# arwe.net
KiCad netlist of a schematic drawn in EAGLE
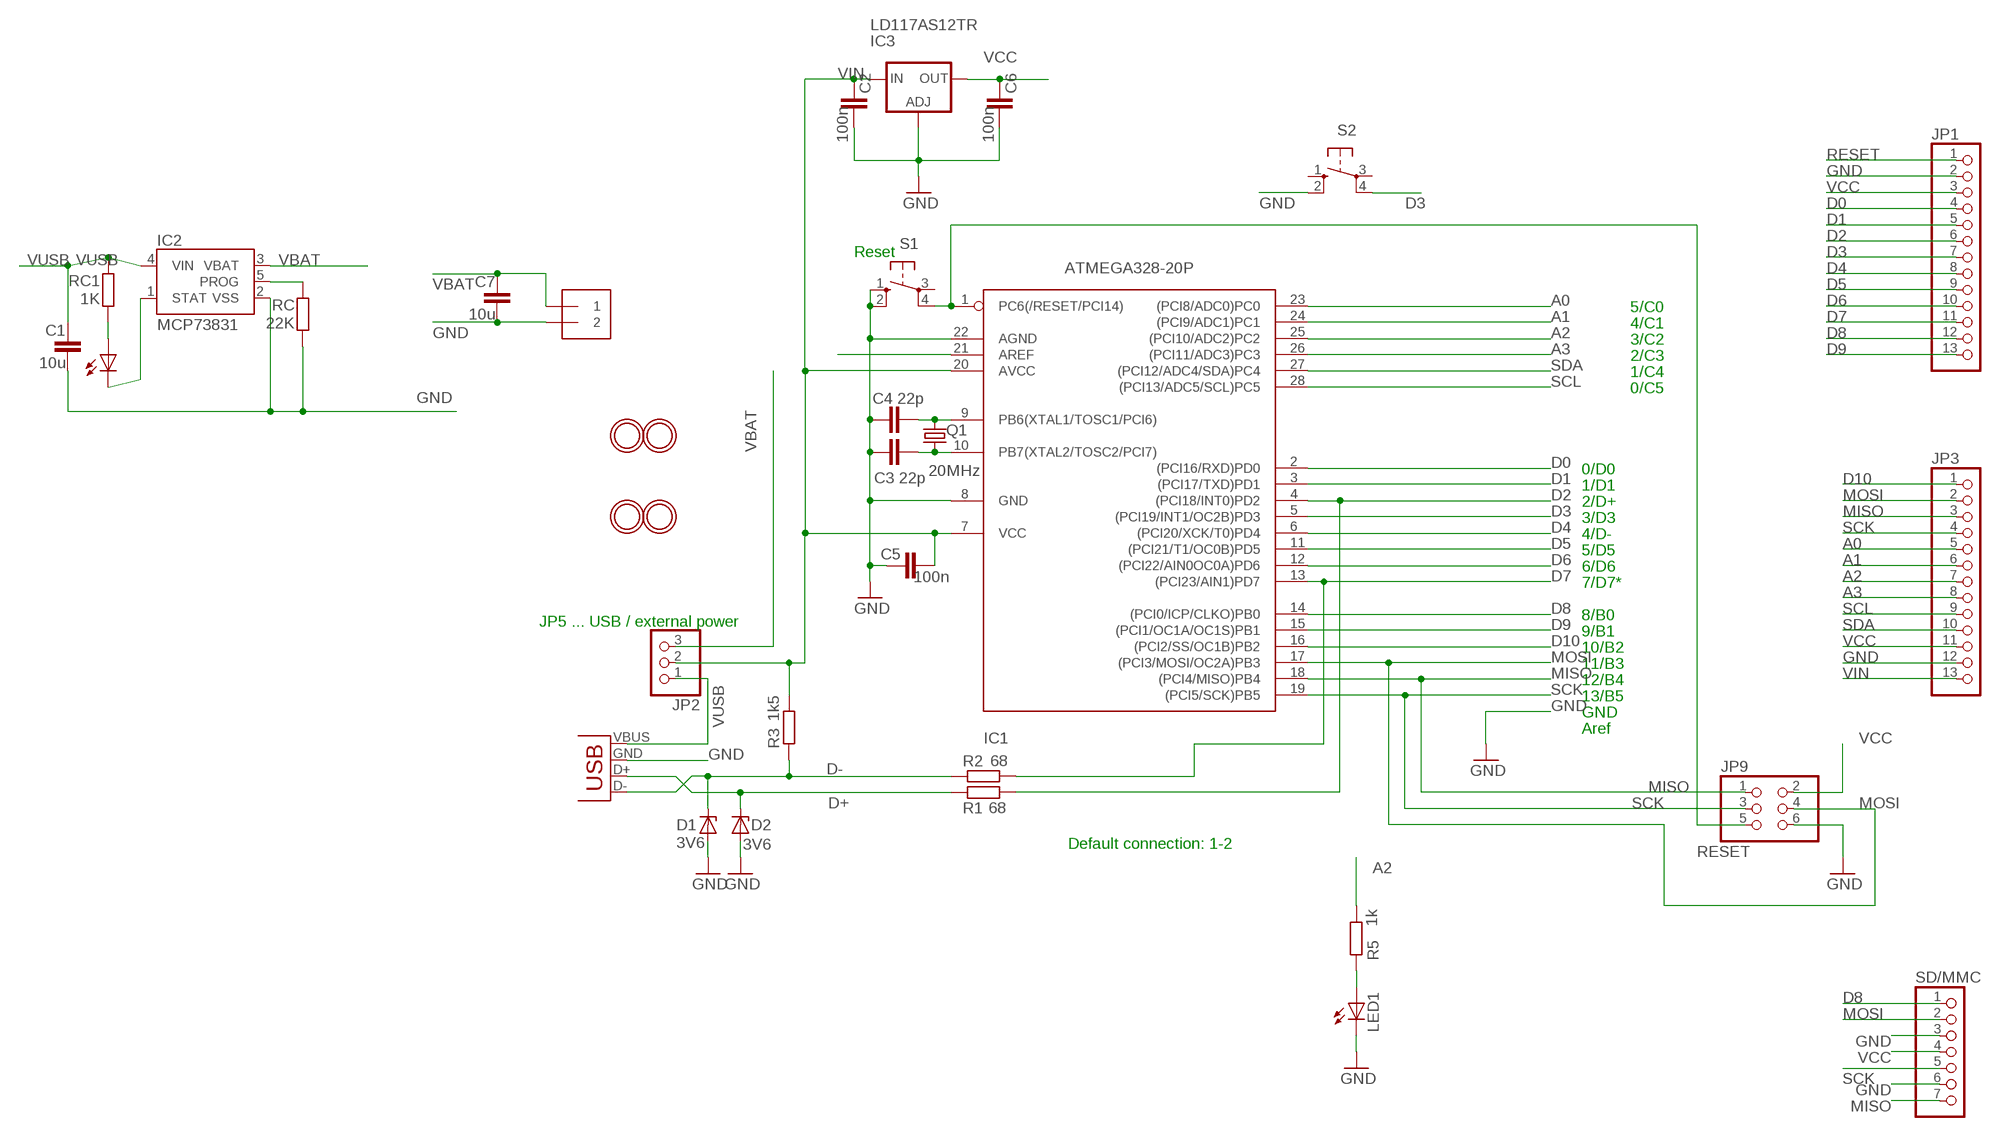
[diagram p0: schematic, sheet 1]

(export (version "E")
  (design (tool "Eeschema 10.0.6"))
  (components
    (comp (ref "C1")
      (value "10u")
      (footprint "eagle-import:C0603")
      (libsource (lib "eagle-import") (part "resistor_C-EUC0603"))
    )
    (comp (ref "C2")
      (value "100n")
      (footprint "eagle-import:C025-024X044")
      (libsource (lib "eagle-import") (part "C-EU025-024X044"))
    )
    (comp (ref "C3")
      (value "22p")
      (footprint "eagle-import:C025-024X044")
      (libsource (lib "eagle-import") (part "C-EU025-024X044"))
    )
    (comp (ref "C4")
      (value "22p")
      (footprint "eagle-import:C025-024X044")
      (libsource (lib "eagle-import") (part "C-EU025-024X044"))
    )
    (comp (ref "C5")
      (value "100n")
      (footprint "eagle-import:C025-024X044")
      (libsource (lib "eagle-import") (part "C-EU025-024X044"))
    )
    (comp (ref "C6")
      (value "100n")
      (footprint "eagle-import:C025-024X044")
      (libsource (lib "eagle-import") (part "C-EU025-024X044"))
    )
    (comp (ref "C7")
      (value "10u")
      (footprint "eagle-import:C0603")
      (libsource (lib "eagle-import") (part "resistor_C-EUC0603"))
    )
    (comp (ref "CHG")
      (value "0805")
      (footprint "eagle-import:CHIPLED_0603")
      (libsource (lib "eagle-import") (part "LEDCHIPLED_0603"))
    )
    (comp (ref "D1")
      (value "3V6")
      (footprint "eagle-import:ZDIO-5")
      (libsource (lib "eagle-import") (part "ZENER-DIODEZD-5"))
    )
    (comp (ref "D2")
      (value "3V6")
      (footprint "eagle-import:ZDIO-5")
      (libsource (lib "eagle-import") (part "ZENER-DIODEZD-5"))
    )
    (comp (ref "IC1")
      (value "ATMEGA328-20P")
      (footprint "eagle-import:DIL28-3")
      (libsource (lib "eagle-import") (part "ATMEGA168P-20"))
    )
    (comp (ref "IC2")
      (value "MCP73831")
      (footprint "eagle-import:SOT23-5")
      (libsource (lib "eagle-import") (part "MCP73831"))
    )
    (comp (ref "IC3")
      (value "LD117AS12TR")
      (footprint "eagle-import:SOT223")
      (libsource (lib "eagle-import") (part "LD117A?S12TR"))
    )
    (comp (ref "J1")
      (value "1X2-3.5MM")
      (footprint "eagle-import:1X2-3.5MM")
      (libsource (lib "eagle-import") (part "1X2-3.5MM"))
    )
    (comp (ref "JP1")
      (value "PINHD-1X13")
      (footprint "eagle-import:1X13")
      (libsource (lib "eagle-import") (part "PINHD-1X13"))
    )
    (comp (ref "JP2")
      (value "PINHD-1X3")
      (footprint "eagle-import:1X03")
      (libsource (lib "eagle-import") (part "PINHD-1X3"))
    )
    (comp (ref "JP3")
      (value "PINHD-1X13")
      (footprint "eagle-import:1X13")
      (libsource (lib "eagle-import") (part "PINHD-1X13"))
    )
    (comp (ref "JP9")
      (value "PINHD-2X3")
      (footprint "eagle-import:2X03")
      (libsource (lib "eagle-import") (part "PINHD-2X3"))
    )
    (comp (ref "LED1")
      (value "LED3MM")
      (footprint "eagle-import:LED3MM")
      (libsource (lib "eagle-import") (part "LED3MM"))
    )
    (comp (ref "Q1")
      (value "20MHz")
      (footprint "eagle-import:HC49_S")
      (libsource (lib "eagle-import") (part "CRYSTALHC49S"))
    )
    (comp (ref "R1")
      (value "68")
      (footprint "eagle-import:0204_5")
      (libsource (lib "eagle-import") (part "R-EU_0204/5"))
    )
    (comp (ref "R2")
      (value "68")
      (footprint "eagle-import:0204_5")
      (libsource (lib "eagle-import") (part "R-EU_0204/5"))
    )
    (comp (ref "R3")
      (value "1k5")
      (footprint "eagle-import:0204_5")
      (libsource (lib "eagle-import") (part "R-EU_0204/5"))
    )
    (comp (ref "R5")
      (value "1k")
      (footprint "eagle-import:0204_5")
      (libsource (lib "eagle-import") (part "R-EU_0204/5"))
    )
    (comp (ref "RC")
      (value "22K")
      (footprint "eagle-import:R0603")
      (libsource (lib "eagle-import") (part "R-EU_R0603"))
    )
    (comp (ref "RC1")
      (value "1K")
      (footprint "eagle-import:R0603")
      (libsource (lib "eagle-import") (part "R-EU_R0603"))
    )
    (comp (ref "S1")
      (value "10-XX")
      (footprint "eagle-import:B3F-10XX")
      (fields (field (name "MPN") "B3F-1000"))
      (libsource (lib "eagle-import") (part "10-XX"))
    )
    (comp (ref "S2")
      (value "10-XX")
      (footprint "eagle-import:B3F-10XX")
      (fields
        (field (name "MPN") "B3F-1000")
        (field (name "MPN_1") "B3F-1000")
        (field (name "OC_FARNELL") "176432")
        (field (name "OC_NEWARK") "36M3542")
      )
      (libsource (lib "eagle-import") (part "10-XX"))
    )
    (comp (ref "SD/MMC")
      (value "PINHD-1X7")
      (footprint "eagle-import:1X07")
      (libsource (lib "eagle-import") (part "PINHD-1X7"))
    )
    (comp (ref "U$2")
      (value "MOUNTINGHOLE3.0THIN")
      (footprint "eagle-import:MOUNTINGHOLE_3.0_PLATEDTHIN")
      (libsource (lib "eagle-import") (part "MOUNTINGHOLE3.0THIN"))
    )
    (comp (ref "U$3")
      (value "MOUNTINGHOLE3.0THIN")
      (footprint "eagle-import:MOUNTINGHOLE_3.0_PLATEDTHIN")
      (libsource (lib "eagle-import") (part "MOUNTINGHOLE3.0THIN"))
    )
    (comp (ref "U$4")
      (value "MOUNTINGHOLE3.0THIN")
      (footprint "eagle-import:MOUNTINGHOLE_3.0_PLATEDTHIN")
      (libsource (lib "eagle-import") (part "MOUNTINGHOLE3.0THIN"))
    )
    (comp (ref "U$5")
      (value "MOUNTINGHOLE3.0THIN")
      (footprint "eagle-import:MOUNTINGHOLE_3.0_PLATEDTHIN")
      (libsource (lib "eagle-import") (part "MOUNTINGHOLE3.0THIN"))
    )
    (comp (ref "X1")
      (value "USB-A-H")
      (footprint "eagle-import:USB-A-H")
      (libsource (lib "eagle-import") (part "USB-A-H"))
    )
  )
  (nets
    (net (code "1") (name "/A0") (class "Default")
      (node (ref "IC1") (pin "23") (pinfunction "(PCI8/ADC0)PC0_23") (pintype "bidirectional"))
      (node (ref "JP3") (pin "5") (pinfunction "5_5") (pintype "passive"))
    )
    (net (code "2") (name "/A1") (class "Default")
      (node (ref "IC1") (pin "24") (pinfunction "(PCI9/ADC1)PC1_24") (pintype "bidirectional"))
      (node (ref "JP3") (pin "6") (pinfunction "6_6") (pintype "passive"))
    )
    (net (code "3") (name "/A2") (class "Default")
      (node (ref "IC1") (pin "25") (pinfunction "(PCI10/ADC2)PC2_25") (pintype "bidirectional"))
      (node (ref "JP3") (pin "7") (pinfunction "7_7") (pintype "passive"))
      (node (ref "R5") (pin "1") (pinfunction "1_1") (pintype "passive"))
    )
    (net (code "4") (name "/A3") (class "Default")
      (node (ref "IC1") (pin "26") (pinfunction "(PCI11/ADC3)PC3_26") (pintype "bidirectional"))
      (node (ref "JP3") (pin "8") (pinfunction "8_8") (pintype "passive"))
    )
    (net (code "5") (name "/D+") (class "Default")
      (node (ref "D2") (pin "C") (pinfunction "C_C") (pintype "passive"))
      (node (ref "R1") (pin "1") (pinfunction "1_1") (pintype "passive"))
      (node (ref "X1") (pin "D+") (pinfunction "D-_D+") (pintype "bidirectional"))
    )
    (net (code "6") (name "/D-") (class "Default")
      (node (ref "D1") (pin "C") (pinfunction "C_C") (pintype "passive"))
      (node (ref "R2") (pin "1") (pinfunction "1_1") (pintype "passive"))
      (node (ref "R3") (pin "1") (pinfunction "1_1") (pintype "passive"))
      (node (ref "X1") (pin "D-") (pinfunction "D+_D-") (pintype "bidirectional"))
    )
    (net (code "7") (name "/D0") (class "Default")
      (node (ref "IC1") (pin "2") (pinfunction "(PCI16/RXD)PD0_2") (pintype "bidirectional"))
      (node (ref "JP1") (pin "4") (pinfunction "4_4") (pintype "passive"))
    )
    (net (code "8") (name "/D1") (class "Default")
      (node (ref "IC1") (pin "3") (pinfunction "(PCI17/TXD)PD1_3") (pintype "bidirectional"))
      (node (ref "JP1") (pin "5") (pinfunction "5_5") (pintype "passive"))
    )
    (net (code "9") (name "/D2") (class "Default")
      (node (ref "IC1") (pin "4") (pinfunction "(PCI18/INT0)PD2_4") (pintype "bidirectional"))
      (node (ref "JP1") (pin "6") (pinfunction "6_6") (pintype "passive"))
      (node (ref "R1") (pin "2") (pinfunction "2_2") (pintype "passive"))
    )
    (net (code "10") (name "/D3") (class "Default")
      (node (ref "IC1") (pin "5") (pinfunction "(PCI19/INT1/OC2B)PD3_5") (pintype "bidirectional"))
      (node (ref "JP1") (pin "7") (pinfunction "7_7") (pintype "passive"))
      (node (ref "S2") (pin "4") (pinfunction "P1_4") (pintype "passive"))
    )
    (net (code "11") (name "/D4") (class "Default")
      (node (ref "IC1") (pin "6") (pinfunction "(PCI20/XCK/T0)PD4_6") (pintype "bidirectional"))
      (node (ref "JP1") (pin "8") (pinfunction "8_8") (pintype "passive"))
    )
    (net (code "12") (name "/D5") (class "Default")
      (node (ref "IC1") (pin "11") (pinfunction "(PCI21/T1/OC0B)PD5_11") (pintype "bidirectional"))
      (node (ref "JP1") (pin "9") (pinfunction "9_9") (pintype "passive"))
    )
    (net (code "13") (name "/D6") (class "Default")
      (node (ref "IC1") (pin "12") (pinfunction "(PCI22/AIN0OC0A)PD6_12") (pintype "bidirectional"))
      (node (ref "JP1") (pin "10") (pinfunction "10_10") (pintype "passive"))
    )
    (net (code "14") (name "/D7") (class "Default")
      (node (ref "IC1") (pin "13") (pinfunction "(PCI23/AIN1)PD7_13") (pintype "bidirectional"))
      (node (ref "JP1") (pin "11") (pinfunction "11_11") (pintype "passive"))
      (node (ref "R2") (pin "2") (pinfunction "2_2") (pintype "passive"))
    )
    (net (code "15") (name "/D8") (class "Default")
      (node (ref "IC1") (pin "14") (pinfunction "(PCI0/ICP/CLKO)PB0_14") (pintype "bidirectional"))
      (node (ref "JP1") (pin "12") (pinfunction "12_12") (pintype "passive"))
      (node (ref "SD/MMC") (pin "1") (pinfunction "1_1") (pintype "passive"))
    )
    (net (code "16") (name "/D9") (class "Default")
      (node (ref "IC1") (pin "15") (pinfunction "(PCI1/OC1A/OC1S)PB1_15") (pintype "bidirectional"))
      (node (ref "JP1") (pin "13") (pinfunction "13_13") (pintype "passive"))
    )
    (net (code "17") (name "/D10") (class "Default")
      (node (ref "IC1") (pin "16") (pinfunction "(PCI2/SS/OC1B)PB2_16") (pintype "bidirectional"))
      (node (ref "JP3") (pin "1") (pinfunction "1_1") (pintype "passive"))
    )
    (net (code "18") (name "/MISO") (class "Default")
      (node (ref "IC1") (pin "18") (pinfunction "(PCI4/MISO)PB4_18") (pintype "bidirectional"))
      (node (ref "JP3") (pin "3") (pinfunction "3_3") (pintype "passive"))
      (node (ref "JP9") (pin "1") (pinfunction "1_1") (pintype "passive"))
      (node (ref "SD/MMC") (pin "7") (pinfunction "7_7") (pintype "passive"))
    )
    (net (code "19") (name "/MOSI") (class "Default")
      (node (ref "IC1") (pin "17") (pinfunction "(PCI3/MOSI/OC2A)PB3_17") (pintype "bidirectional"))
      (node (ref "JP3") (pin "2") (pinfunction "2_2") (pintype "passive"))
      (node (ref "JP9") (pin "4") (pinfunction "4_4") (pintype "passive"))
      (node (ref "SD/MMC") (pin "2") (pinfunction "2_2") (pintype "passive"))
    )
    (net (code "20") (name "/RESET") (class "Default")
      (node (ref "IC1") (pin "1") (pinfunction "PC6(/RESET/PCI14)_1") (pintype "bidirectional"))
      (node (ref "JP1") (pin "1") (pinfunction "1_1") (pintype "passive"))
      (node (ref "JP9") (pin "5") (pinfunction "5_5") (pintype "passive"))
      (node (ref "S1") (pin "4") (pinfunction "P1_4") (pintype "passive"))
    )
    (net (code "21") (name "/SCK") (class "Default")
      (node (ref "IC1") (pin "19") (pinfunction "(PCI5/SCK)PB5_19") (pintype "bidirectional"))
      (node (ref "JP3") (pin "4") (pinfunction "4_4") (pintype "passive"))
      (node (ref "JP9") (pin "3") (pinfunction "3_3") (pintype "passive"))
      (node (ref "SD/MMC") (pin "5") (pinfunction "5_5") (pintype "passive"))
    )
    (net (code "22") (name "/SCL") (class "Default")
      (node (ref "IC1") (pin "28") (pinfunction "(PCI13/ADC5/SCL)PC5_28") (pintype "bidirectional"))
      (node (ref "JP3") (pin "9") (pinfunction "9_9") (pintype "passive"))
    )
    (net (code "23") (name "/SDA") (class "Default")
      (node (ref "IC1") (pin "27") (pinfunction "(PCI12/ADC4/SDA)PC4_27") (pintype "bidirectional"))
      (node (ref "JP3") (pin "10") (pinfunction "10_10") (pintype "passive"))
    )
    (net (code "24") (name "/VBAT") (class "Default")
      (node (ref "C7") (pin "1") (pinfunction "1_1") (pintype "passive"))
      (node (ref "IC2") (pin "3") (pinfunction "VBAT_3") (pintype "power_in"))
      (node (ref "J1") (pin "1") (pinfunction "1_1") (pintype "passive"))
      (node (ref "JP2") (pin "3") (pinfunction "3_3") (pintype "passive"))
    )
    (net (code "25") (name "/VCC") (class "Default")
      (node (ref "C6") (pin "1") (pinfunction "1_1") (pintype "passive"))
      (node (ref "IC3") (pin "4") (pinfunction "OUT_4") (pintype "passive"))
      (node (ref "JP1") (pin "3") (pinfunction "3_3") (pintype "passive"))
      (node (ref "JP3") (pin "11") (pinfunction "11_11") (pintype "passive"))
      (node (ref "JP9") (pin "2") (pinfunction "2_2") (pintype "passive"))
      (node (ref "SD/MMC") (pin "4") (pinfunction "4_4") (pintype "passive"))
    )
    (net (code "26") (name "/VIN") (class "Default")
      (node (ref "C2") (pin "1") (pinfunction "1_1") (pintype "passive"))
      (node (ref "C5") (pin "2") (pinfunction "2_2") (pintype "passive"))
      (node (ref "IC1") (pin "20") (pinfunction "AVCC_20") (pintype "bidirectional"))
      (node (ref "IC1") (pin "7") (pinfunction "VCC_7") (pintype "bidirectional"))
      (node (ref "IC3") (pin "3") (pinfunction "IN_3") (pintype "input"))
      (node (ref "JP2") (pin "2") (pinfunction "2_2") (pintype "passive"))
      (node (ref "JP3") (pin "13") (pinfunction "13_13") (pintype "passive"))
      (node (ref "R3") (pin "2") (pinfunction "2_2") (pintype "passive"))
    )
    (net (code "27") (name "/VUSB") (class "Default")
      (node (ref "C1") (pin "1") (pinfunction "1_1") (pintype "passive"))
      (node (ref "IC2") (pin "4") (pinfunction "VIN_4") (pintype "power_in"))
      (node (ref "JP2") (pin "1") (pinfunction "1_1") (pintype "passive"))
      (node (ref "RC1") (pin "2") (pinfunction "2_2") (pintype "passive"))
      (node (ref "X1") (pin "VBUS") (pinfunction "GND_VBUS") (pintype "bidirectional"))
    )
    (net (code "28") (name "GND") (class "Default")
      (node (ref "C1") (pin "2") (pinfunction "2_2") (pintype "passive"))
      (node (ref "C2") (pin "2") (pinfunction "2_2") (pintype "passive"))
      (node (ref "C3") (pin "1") (pinfunction "1_1") (pintype "passive"))
      (node (ref "C4") (pin "1") (pinfunction "1_1") (pintype "passive"))
      (node (ref "C5") (pin "1") (pinfunction "1_1") (pintype "passive"))
      (node (ref "C6") (pin "2") (pinfunction "2_2") (pintype "passive"))
      (node (ref "C7") (pin "2") (pinfunction "2_2") (pintype "passive"))
      (node (ref "D1") (pin "A") (pinfunction "A_A") (pintype "passive"))
      (node (ref "D2") (pin "A") (pinfunction "A_A") (pintype "passive"))
      (node (ref "IC1") (pin "22") (pinfunction "AGND_22") (pintype "bidirectional"))
      (node (ref "IC1") (pin "8") (pinfunction "GND_8") (pintype "bidirectional"))
      (node (ref "IC2") (pin "2") (pinfunction "VSS_2") (pintype "power_in"))
      (node (ref "IC3") (pin "1") (pinfunction "ADJ_1") (pintype "input"))
      (node (ref "J1") (pin "2") (pinfunction "2_2") (pintype "passive"))
      (node (ref "JP1") (pin "2") (pinfunction "2_2") (pintype "passive"))
      (node (ref "JP3") (pin "12") (pinfunction "12_12") (pintype "passive"))
      (node (ref "JP9") (pin "6") (pinfunction "6_6") (pintype "passive"))
      (node (ref "LED1") (pin "K") (pinfunction "C_K") (pintype "passive"))
      (node (ref "RC") (pin "1") (pinfunction "1_1") (pintype "passive"))
      (node (ref "S1") (pin "1") (pinfunction "S_1") (pintype "passive"))
      (node (ref "S1") (pin "2") (pinfunction "S1_2") (pintype "passive"))
      (node (ref "S2") (pin "2") (pinfunction "S1_2") (pintype "passive"))
      (node (ref "SD/MMC") (pin "3") (pinfunction "3_3") (pintype "passive"))
      (node (ref "SD/MMC") (pin "6") (pinfunction "6_6") (pintype "passive"))
      (node (ref "X1") (pin "GND") (pinfunction "VBUS_GND") (pintype "bidirectional"))
    )
    (net (code "29") (name "Net-(CHG-PadA)") (class "Default")
      (node (ref "CHG") (pin "A") (pinfunction "A_A") (pintype "passive"))
      (node (ref "RC1") (pin "1") (pinfunction "1_1") (pintype "passive"))
    )
    (net (code "30") (name "Net-(IC1-PB6(XTAL1{slash}TOSC1{slash}PCI6))") (class "Default")
      (node (ref "C4") (pin "2") (pinfunction "2_2") (pintype "passive"))
      (node (ref "IC1") (pin "9") (pinfunction "PB6(XTAL1/TOSC1/PCI6)_9") (pintype "bidirectional"))
      (node (ref "Q1") (pin "2") (pinfunction "2_2") (pintype "passive"))
    )
    (net (code "31") (name "Net-(IC1-PB7(XTAL2{slash}TOSC2{slash}PCI7))") (class "Default")
      (node (ref "C3") (pin "2") (pinfunction "2_2") (pintype "passive"))
      (node (ref "IC1") (pin "10") (pinfunction "PB7(XTAL2/TOSC2/PCI7)_10") (pintype "bidirectional"))
      (node (ref "Q1") (pin "1") (pinfunction "1_1") (pintype "passive"))
    )
    (net (code "32") (name "Net-(IC2-PROG)") (class "Default")
      (node (ref "IC2") (pin "5") (pinfunction "PROG_5") (pintype "input"))
      (node (ref "RC") (pin "2") (pinfunction "2_2") (pintype "passive"))
    )
    (net (code "33") (name "Net-(IC2-STAT)") (class "Default")
      (node (ref "CHG") (pin "C") (pinfunction "C_C") (pintype "passive"))
      (node (ref "IC2") (pin "1") (pinfunction "STAT_1") (pintype "output"))
    )
    (net (code "34") (name "Net-(LED1-PadA)") (class "Default")
      (node (ref "LED1") (pin "A") (pinfunction "A_A") (pintype "passive"))
      (node (ref "R5") (pin "2") (pinfunction "2_2") (pintype "passive"))
    )
    (net (code "35") (name "unconnected-(IC1-AREF-Pad21)") (class "Default")
      (node (ref "IC1") (pin "21") (pinfunction "AREF_21") (pintype "bidirectional"))
    )
    (net (code "36") (name "unconnected-(S1-P-Pad3)") (class "Default")
      (node (ref "S1") (pin "3") (pinfunction "P_3") (pintype "passive"))
    )
    (net (code "37") (name "unconnected-(S2-P-Pad3)") (class "Default")
      (node (ref "S2") (pin "3") (pinfunction "P_3") (pintype "passive"))
    )
    (net (code "38") (name "unconnected-(S2-S-Pad1)") (class "Default")
      (node (ref "S2") (pin "1") (pinfunction "S_1") (pintype "passive"))
    )
  )
)
